# CH32V203F8P6-R0.net
KiCad netlist of a schematic drawn in Altium Designer
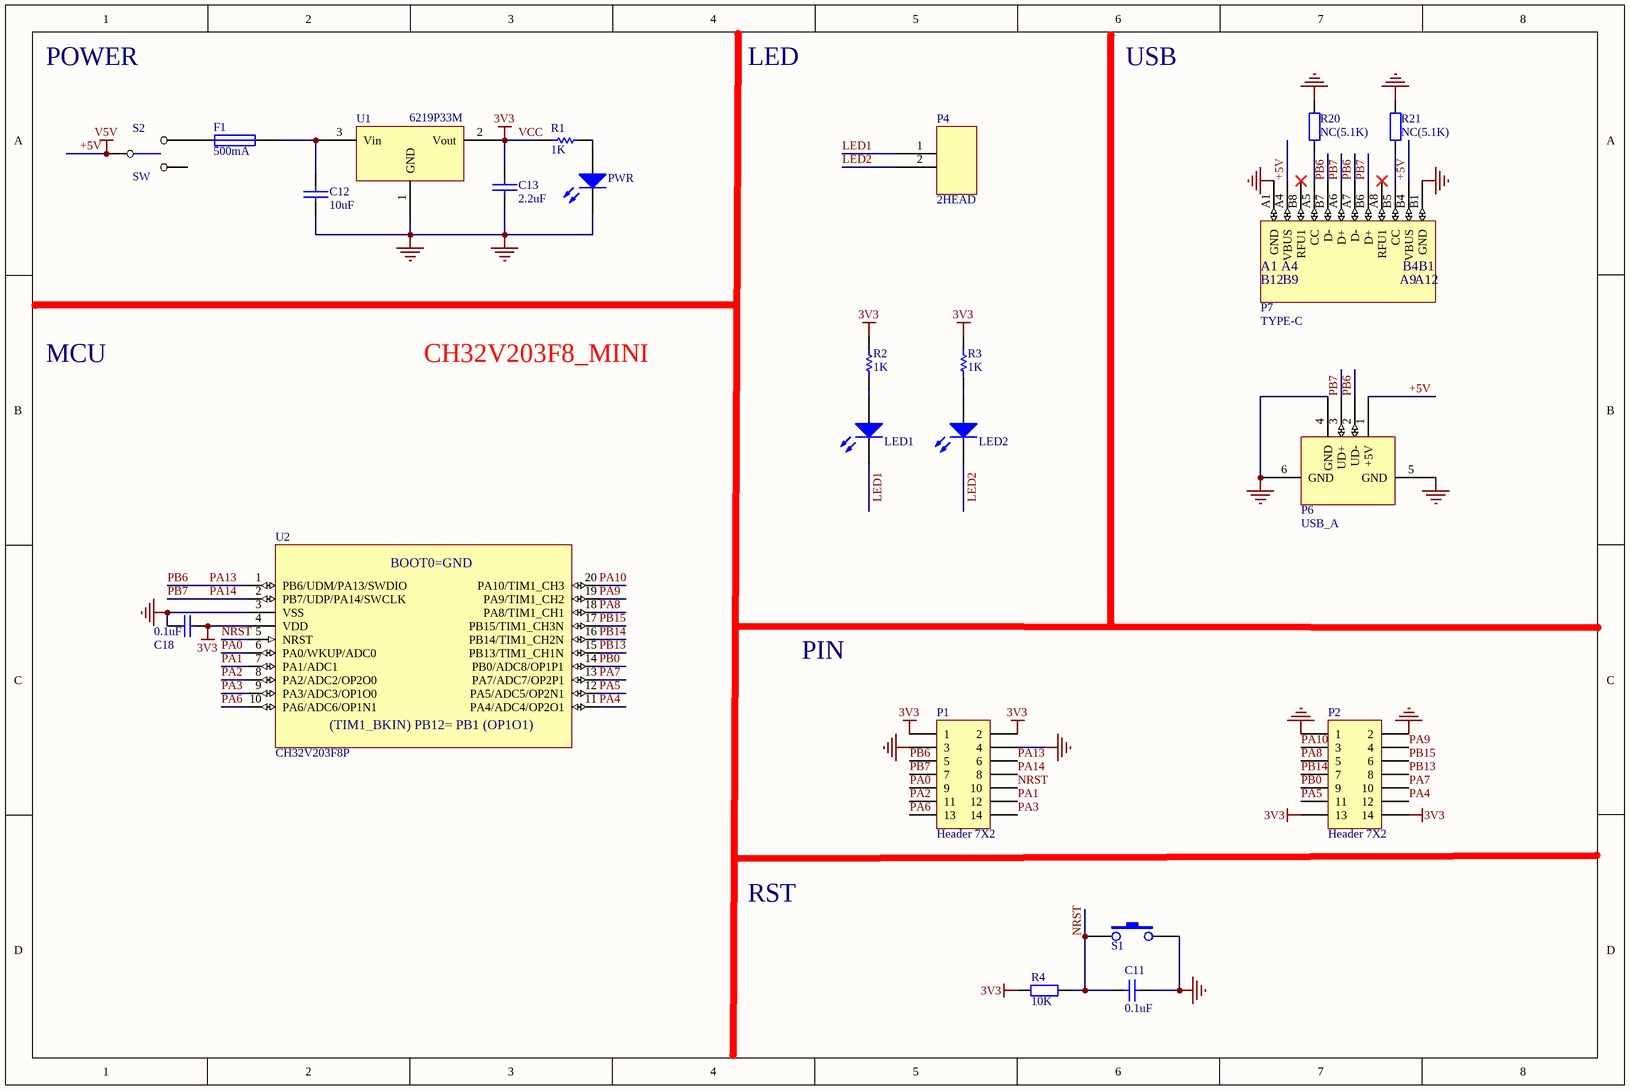
[diagram p0: CH32V203F8P6-R0.SchDoc]

(export (version "E")
  (design (tool "Eeschema 10.0.6"))
  (components
    (comp (ref "C11")
      (value "0.1uF")
      (footprint "0603_C")
      (description "Capacitor")
      (fields (field (name "PUBLISHER") "Altium Limited"))
      (libsource (lib "*") (part "Cap"))
    )
    (comp (ref "C12")
      (value "10uF")
      (footprint "3216_C")
      (description "Capacitor")
      (libsource (lib "wch_sch_others") (part "CAP"))
    )
    (comp (ref "C13")
      (value "2.2uF")
      (footprint "0603_C")
      (description "Capacitor")
      (libsource (lib "wch_sch_others") (part "CAP"))
    )
    (comp (ref "C18")
      (value "0.1uF")
      (footprint "0603_C")
      (description "Capacitor")
      (fields (field (name "PUBLISHER") "Altium Limited"))
      (libsource (lib "*") (part "Cap"))
    )
    (comp (ref "F1")
      (value "500mA")
      (footprint "0603")
      (description "Fuse")
      (libsource (lib "*") (part "FUSE1"))
    )
    (comp (ref "LED1")
      (value "LED1   blue")
      (footprint "0603+")
      (description "Typical INFRARED GaAs LED")
      (fields (field (name "PUBLISHER") "Altium Limited"))
      (libsource (lib "*") (part "LED0"))
    )
    (comp (ref "LED2")
      (value "LED2  blue")
      (footprint "0603+")
      (description "Typical INFRARED GaAs LED")
      (fields (field (name "PUBLISHER") "Altium Limited"))
      (libsource (lib "*") (part "LED0"))
    )
    (comp (ref "P1")
      (value "Header 7X2")
      (footprint "IDC14-2.54mm")
      (description "Header, 7-Pin, Dual row")
      (fields (field (name "PUBLISHER") "Altium Limited"))
      (libsource (lib "Miscellaneous Connectors") (part "Header 7X2"))
    )
    (comp (ref "P2")
      (value "Header 7X2")
      (footprint "IDC14-2.54mm")
      (description "Header, 7-Pin, Dual row")
      (fields (field (name "PUBLISHER") "Altium Limited"))
      (libsource (lib "Miscellaneous Connectors") (part "Header 7X2"))
    )
    (comp (ref "P4") (value "2HEAD") (footprint "SIP2-2.54mm") (libsource (lib "*") (part "2HEAD")))
    (comp (ref "P6")
      (value "USB_A")
      (footprint "USBAF")
      (description "USB Port")
      (libsource (lib "*") (part "USB"))
    )
    (comp (ref "P7")
      (value "TYPE-C")
      (footprint "TYPE-C-Receptacle-2.0")
      (libsource (lib "*") (part "TYPE-C1"))
    )
    (comp (ref "PWR")
      (value "POWER  red")
      (footprint "0603+")
      (description "Typical INFRARED GaAs LED")
      (fields (field (name "PUBLISHER") "Altium Limited"))
      (libsource (lib "") (part "LED0_1"))
    )
    (comp (ref "R1")
      (value "1K")
      (footprint "0603")
      (description "Semiconductor Resistor")
      (fields (field (name "PUBLISHER") "Altium Limited"))
      (libsource (lib "*") (part "Res Semi"))
    )
    (comp (ref "R2")
      (value "1K")
      (footprint "0603")
      (description "Semiconductor Resistor")
      (fields (field (name "PUBLISHER") "Altium Limited"))
      (libsource (lib "*") (part "Res Semi"))
    )
    (comp (ref "R3")
      (value "1K")
      (footprint "0603")
      (description "Semiconductor Resistor")
      (fields (field (name "PUBLISHER") "Altium Limited"))
      (libsource (lib "*") (part "Res Semi"))
    )
    (comp (ref "R4")
      (value "10K")
      (footprint "0603")
      (description "Resistor")
      (fields (field (name "PUBLISHER") "Altium Limited"))
      (libsource (lib "*") (part "Res2"))
    )
    (comp (ref "R20")
      (value "NC(5.1K)")
      (footprint "0603")
      (description "Resistor")
      (libsource (lib "Miscellaneous Devices") (part "Res2"))
    )
    (comp (ref "R21")
      (value "NC(5.1K)")
      (footprint "0603")
      (description "Resistor")
      (libsource (lib "Miscellaneous Devices") (part "Res2"))
    )
    (comp (ref "S1") (value "NRST") (footprint "SMD_6.1x3.65x2.5mm-KEY") (libsource (lib "*") (part "KEY")))
    (comp (ref "S2") (value "SW") (footprint "KEY2") (libsource (lib "*") (part "SW")))
    (comp (ref "U1")
      (value "6219P33M")
      (footprint "SOT-23")
      (libsource (lib "wch_sch_others") (part "6219P33M"))
    )
    (comp (ref "U2")
      (value "CH32V203F8P")
      (footprint "TSSOP20")
      (description "RISC-V LMD-MCU, 144MHz, for motor")
      (libsource (lib "CHXXX") (part "CH32V203F8P"))
    )
  )
  (nets
    (net (code "2") (name "/LED1") (class "Default")
      (node (ref "LED1") (pin "2") (pinfunction "K_2") (pintype "passive"))
      (node (ref "P4") (pin "1") (pintype "passive"))
    )
    (net (code "3") (name "/LED2") (class "Default")
      (node (ref "LED2") (pin "2") (pinfunction "K_2") (pintype "passive"))
      (node (ref "P4") (pin "2") (pintype "passive"))
    )
    (net (code "4") (name "/NRST") (class "Default")
      (node (ref "C11") (pin "2") (pinfunction "2_2") (pintype "passive"))
      (node (ref "P1") (pin "10") (pinfunction "10_10") (pintype "passive"))
      (node (ref "R4") (pin "1") (pinfunction "1_1") (pintype "passive"))
      (node (ref "S1") (pin "1") (pinfunction "1_1") (pintype "passive"))
      (node (ref "U2") (pin "5") (pinfunction "NRST_5") (pintype "input"))
    )
    (net (code "5") (name "/PA0") (class "Default")
      (node (ref "P1") (pin "9") (pinfunction "9_9") (pintype "passive"))
      (node (ref "U2") (pin "6") (pinfunction "PA0/WKUP/ADC0_6") (pintype "bidirectional"))
    )
    (net (code "6") (name "/PA1") (class "Default")
      (node (ref "P1") (pin "12") (pinfunction "12_12") (pintype "passive"))
      (node (ref "U2") (pin "7") (pinfunction "PA1/ADC1_7") (pintype "bidirectional"))
    )
    (net (code "7") (name "/PA2") (class "Default")
      (node (ref "P1") (pin "11") (pinfunction "11_11") (pintype "passive"))
      (node (ref "U2") (pin "8") (pinfunction "PA2/ADC2/OP2O0_8") (pintype "bidirectional"))
    )
    (net (code "8") (name "/PA3") (class "Default")
      (node (ref "P1") (pin "14") (pinfunction "14_14") (pintype "passive"))
      (node (ref "U2") (pin "9") (pinfunction "PA3/ADC3/OP1O0_9") (pintype "bidirectional"))
    )
    (net (code "9") (name "/PA4") (class "Default")
      (node (ref "P2") (pin "12") (pinfunction "12_12") (pintype "passive"))
      (node (ref "U2") (pin "11") (pinfunction "PA4/ADC4/OP2O1_11") (pintype "bidirectional"))
    )
    (net (code "10") (name "/PA5") (class "Default")
      (node (ref "P2") (pin "11") (pinfunction "11_11") (pintype "passive"))
      (node (ref "U2") (pin "12") (pinfunction "PA5/ADC5/OP2N1_12") (pintype "bidirectional"))
    )
    (net (code "11") (name "/PA6") (class "Default")
      (node (ref "P1") (pin "13") (pinfunction "13_13") (pintype "passive"))
      (node (ref "U2") (pin "10") (pinfunction "PA6/ADC6/OP1N1_10") (pintype "bidirectional"))
    )
    (net (code "12") (name "/PA7") (class "Default")
      (node (ref "P2") (pin "10") (pinfunction "10_10") (pintype "passive"))
      (node (ref "U2") (pin "13") (pinfunction "PA7/ADC7/OP2P1_13") (pintype "bidirectional"))
    )
    (net (code "13") (name "/PA8") (class "Default")
      (node (ref "P2") (pin "5") (pinfunction "5_5") (pintype "passive"))
      (node (ref "U2") (pin "18") (pinfunction "PA8/TIM1_CH1_18") (pintype "bidirectional"))
    )
    (net (code "14") (name "/PA9") (class "Default")
      (node (ref "P2") (pin "4") (pinfunction "4_4") (pintype "passive"))
      (node (ref "U2") (pin "19") (pinfunction "PA9/TIM1_CH2_19") (pintype "bidirectional"))
    )
    (net (code "15") (name "/PA10") (class "Default")
      (node (ref "P2") (pin "3") (pinfunction "3_3") (pintype "passive"))
      (node (ref "U2") (pin "20") (pinfunction "PA10/TIM1_CH3_20") (pintype "bidirectional"))
    )
    (net (code "16") (name "/PA13") (class "Default")
      (node (ref "P1") (pin "5") (pinfunction "5_5") (pintype "passive"))
      (node (ref "P1") (pin "6") (pinfunction "6_6") (pintype "passive"))
      (node (ref "P6") (pin "2") (pinfunction "UD-_2") (pintype "bidirectional"))
      (node (ref "P7") (pin "A7") (pinfunction "D-_A7") (pintype "bidirectional"))
      (node (ref "P7") (pin "B7") (pinfunction "D-_B7") (pintype "bidirectional"))
      (node (ref "U2") (pin "1") (pinfunction "PB6/UDM/PA13/SWDIO_1") (pintype "bidirectional"))
    )
    (net (code "17") (name "/PA14") (class "Default")
      (node (ref "P1") (pin "7") (pinfunction "7_7") (pintype "passive"))
      (node (ref "P1") (pin "8") (pinfunction "8_8") (pintype "passive"))
      (node (ref "P6") (pin "3") (pinfunction "UD+_3") (pintype "bidirectional"))
      (node (ref "P7") (pin "A6") (pinfunction "D+_A6") (pintype "bidirectional"))
      (node (ref "P7") (pin "B6") (pinfunction "D+_B6") (pintype "bidirectional"))
      (node (ref "U2") (pin "2") (pinfunction "PB7/UDP/PA14/SWCLK_2") (pintype "bidirectional"))
    )
    (net (code "18") (name "/PB0") (class "Default")
      (node (ref "P2") (pin "9") (pinfunction "9_9") (pintype "passive"))
      (node (ref "U2") (pin "14") (pinfunction "PB0/ADC8/OP1P1_14") (pintype "bidirectional"))
    )
    (net (code "19") (name "/PB13") (class "Default")
      (node (ref "P2") (pin "8") (pinfunction "8_8") (pintype "passive"))
      (node (ref "U2") (pin "15") (pinfunction "PB13/TIM1_CH1N_15") (pintype "bidirectional"))
    )
    (net (code "20") (name "/PB14") (class "Default")
      (node (ref "P2") (pin "7") (pinfunction "7_7") (pintype "passive"))
      (node (ref "U2") (pin "16") (pinfunction "PB14/TIM1_CH2N_16") (pintype "bidirectional"))
    )
    (net (code "21") (name "/PB15") (class "Default")
      (node (ref "P2") (pin "6") (pinfunction "6_6") (pintype "passive"))
      (node (ref "U2") (pin "17") (pinfunction "PB15/TIM1_CH3N_17") (pintype "bidirectional"))
    )
    (net (code "22") (name "3V3") (class "Default")
      (node (ref "C13") (pin "2") (pinfunction "2_2") (pintype "passive"))
      (node (ref "C18") (pin "2") (pinfunction "2_2") (pintype "passive"))
      (node (ref "P1") (pin "1") (pinfunction "1_1") (pintype "passive"))
      (node (ref "P1") (pin "2") (pinfunction "2_2") (pintype "passive"))
      (node (ref "P2") (pin "13") (pinfunction "13_13") (pintype "passive"))
      (node (ref "P2") (pin "14") (pinfunction "14_14") (pintype "passive"))
      (node (ref "R1") (pin "2") (pinfunction "2_2") (pintype "passive"))
      (node (ref "R2") (pin "1") (pinfunction "1_1") (pintype "passive"))
      (node (ref "R3") (pin "1") (pinfunction "1_1") (pintype "passive"))
      (node (ref "R4") (pin "2") (pinfunction "2_2") (pintype "passive"))
      (node (ref "U1") (pin "2") (pinfunction "Vout_2") (pintype "passive"))
      (node (ref "U2") (pin "4") (pinfunction "VDD_4") (pintype "power_in"))
    )
    (net (code "23") (name "GND") (class "Default")
      (node (ref "C11") (pin "1") (pinfunction "1_1") (pintype "passive"))
      (node (ref "C12") (pin "2") (pinfunction "2_2") (pintype "passive"))
      (node (ref "C13") (pin "1") (pinfunction "1_1") (pintype "passive"))
      (node (ref "C18") (pin "1") (pinfunction "1_1") (pintype "passive"))
      (node (ref "P1") (pin "3") (pinfunction "3_3") (pintype "passive"))
      (node (ref "P1") (pin "4") (pinfunction "4_4") (pintype "passive"))
      (node (ref "P2") (pin "1") (pinfunction "1_1") (pintype "passive"))
      (node (ref "P2") (pin "2") (pinfunction "2_2") (pintype "passive"))
      (node (ref "P6") (pin "4") (pinfunction "GND_4") (pintype "power_in"))
      (node (ref "P6") (pin "5") (pinfunction "GND_5") (pintype "power_in"))
      (node (ref "P6") (pin "6") (pinfunction "GND_6") (pintype "power_in"))
      (node (ref "P7") (pin "A1") (pinfunction "GND_A1") (pintype "bidirectional"))
      (node (ref "P7") (pin "B1") (pinfunction "GND_B1") (pintype "bidirectional"))
      (node (ref "PWR") (pin "2") (pinfunction "K_2") (pintype "passive"))
      (node (ref "R20") (pin "2") (pinfunction "2_2") (pintype "passive"))
      (node (ref "R21") (pin "2") (pinfunction "2_2") (pintype "passive"))
      (node (ref "S1") (pin "2") (pinfunction "2_2") (pintype "passive"))
      (node (ref "U1") (pin "1") (pinfunction "GND_1") (pintype "passive"))
      (node (ref "U2") (pin "3") (pinfunction "VSS_3") (pintype "power_in"))
    )
    (net (code "24") (name "Net-(F1-Pad1)") (class "Default")
      (node (ref "F1") (pin "1") (pinfunction "1_1") (pintype "passive"))
      (node (ref "S2") (pin "3") (pinfunction "3_3") (pintype "passive"))
    )
    (net (code "25") (name "Net-(LED1-A)") (class "Default")
      (node (ref "LED1") (pin "1") (pinfunction "A_1") (pintype "passive"))
      (node (ref "R2") (pin "2") (pinfunction "2_2") (pintype "passive"))
    )
    (net (code "26") (name "Net-(LED2-A)") (class "Default")
      (node (ref "LED2") (pin "1") (pinfunction "A_1") (pintype "passive"))
      (node (ref "R3") (pin "2") (pinfunction "2_2") (pintype "passive"))
    )
    (net (code "27") (name "Net-(P7-CC-PadA5)") (class "Default")
      (node (ref "P7") (pin "A5") (pinfunction "CC_A5") (pintype "bidirectional"))
      (node (ref "R20") (pin "1") (pinfunction "1_1") (pintype "passive"))
    )
    (net (code "28") (name "Net-(P7-CC-PadB5)") (class "Default")
      (node (ref "P7") (pin "B5") (pinfunction "CC_B5") (pintype "bidirectional"))
      (node (ref "R21") (pin "1") (pinfunction "1_1") (pintype "passive"))
    )
    (net (code "29") (name "Net-(PWR-A)") (class "Default")
      (node (ref "PWR") (pin "1") (pinfunction "A_1") (pintype "passive"))
      (node (ref "R1") (pin "1") (pinfunction "1_1") (pintype "passive"))
    )
    (net (code "30") (name "Net-(U1-Vin)") (class "Default")
      (node (ref "C12") (pin "1") (pinfunction "1_1") (pintype "passive"))
      (node (ref "F1") (pin "2") (pinfunction "2_2") (pintype "passive"))
      (node (ref "U1") (pin "3") (pinfunction "Vin_3") (pintype "passive"))
    )
    (net (code "31") (name "V5V") (class "Default")
      (node (ref "P6") (pin "1") (pinfunction "+5V_1") (pintype "power_in"))
      (node (ref "P7") (pin "A4") (pinfunction "VBUS_A4") (pintype "bidirectional"))
      (node (ref "P7") (pin "B4") (pinfunction "VBUS_B4") (pintype "bidirectional"))
      (node (ref "S2") (pin "1") (pinfunction "1_1") (pintype "passive"))
    )
    (net (code "32") (name "unconnected-(P7-RFU1-PadA8)") (class "Default")
      (node (ref "P7") (pin "A8") (pinfunction "RFU1_A8") (pintype "bidirectional+no_connect"))
    )
    (net (code "33") (name "unconnected-(P7-RFU1-PadB8)") (class "Default")
      (node (ref "P7") (pin "B8") (pinfunction "RFU1_B8") (pintype "bidirectional+no_connect"))
    )
    (net (code "34") (name "unconnected-(S2-Pad2)") (class "Default")
      (node (ref "S2") (pin "2") (pinfunction "2_2") (pintype "passive"))
    )
  )
)
